# M1n_name.net
KiCad netlist of a schematic drawn in EAGLE
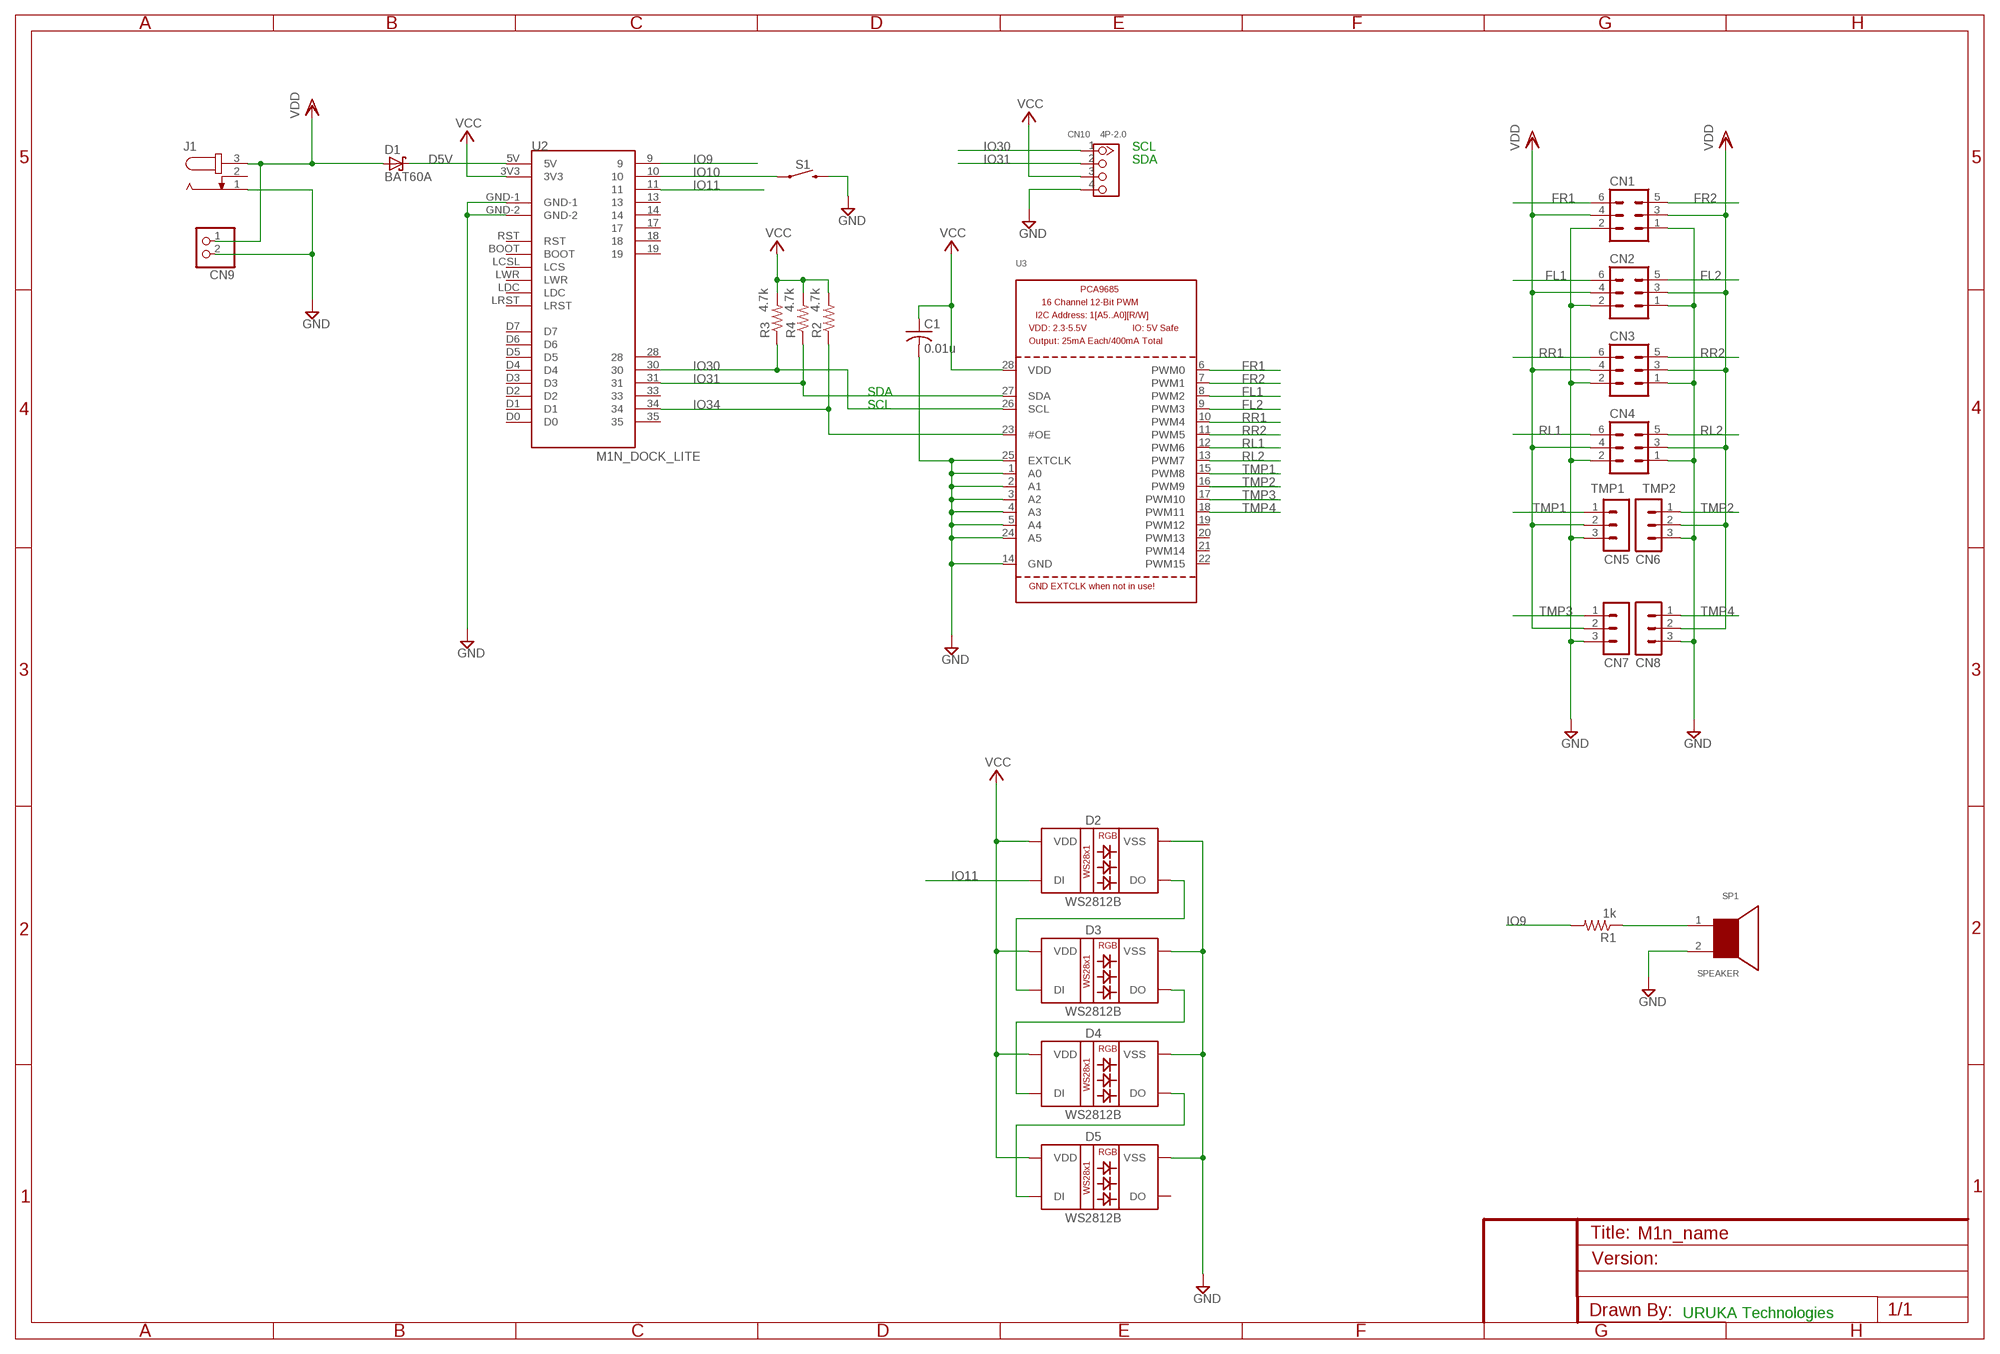
[diagram p0: schematic, sheet 1]

(export (version "E")
  (design (tool "Eeschema 10.0.6"))
  (components
    (comp (ref "C1")
      (value "0.01u")
      (footprint "eagle-import:C0603")
      (libsource (lib "eagle-import") (part "C-USC0603"))
    )
    (comp (ref "CN1")
      (value "MA03-2")
      (footprint "eagle-import:MA03-2")
      (libsource (lib "eagle-import") (part "MA03-2"))
    )
    (comp (ref "CN2")
      (value "MA03-2")
      (footprint "eagle-import:MA03-2")
      (libsource (lib "eagle-import") (part "MA03-2"))
    )
    (comp (ref "CN3")
      (value "MA03-2")
      (footprint "eagle-import:MA03-2")
      (libsource (lib "eagle-import") (part "MA03-2"))
    )
    (comp (ref "CN4")
      (value "MA03-2")
      (footprint "eagle-import:MA03-2")
      (libsource (lib "eagle-import") (part "MA03-2"))
    )
    (comp (ref "CN5")
      (value "MA03-1")
      (footprint "eagle-import:MA03-1")
      (libsource (lib "eagle-import") (part "MA03-1"))
    )
    (comp (ref "CN6")
      (value "MA03-1")
      (footprint "eagle-import:MA03-1")
      (libsource (lib "eagle-import") (part "MA03-1"))
    )
    (comp (ref "CN7")
      (value "MA03-1")
      (footprint "eagle-import:MA03-1")
      (libsource (lib "eagle-import") (part "MA03-1"))
    )
    (comp (ref "CN8")
      (value "MA03-1")
      (footprint "eagle-import:MA03-1")
      (libsource (lib "eagle-import") (part "MA03-1"))
    )
    (comp (ref "CN9")
      (value "JST_2PIN-THM")
      (footprint "eagle-import:JST-PH-2-THM")
      (libsource (lib "eagle-import") (part "JST_2PIN-THM"))
    )
    (comp (ref "CN10")
      (value "4P-2.0")
      (footprint "eagle-import:HW4-2.0")
      (libsource (lib "eagle-import") (part "GROVE-CONNECTOR-DIP(4P-2.0)"))
    )
    (comp (ref "D1")
      (value "BAT60A")
      (footprint "eagle-import:SOD323_ST")
      (libsource (lib "eagle-import") (part "BAT60A"))
    )
    (comp (ref "D2")
      (value "WS2812B")
      (footprint "eagle-import:WS2812_2020")
      (libsource (lib "eagle-import") (part "WS2812_2020"))
    )
    (comp (ref "D3")
      (value "WS2812B")
      (footprint "eagle-import:WS2812_2020")
      (libsource (lib "eagle-import") (part "WS2812_2020"))
    )
    (comp (ref "D4")
      (value "WS2812B")
      (footprint "eagle-import:WS2812_2020")
      (libsource (lib "eagle-import") (part "WS2812_2020"))
    )
    (comp (ref "D5")
      (value "WS2812B")
      (footprint "eagle-import:WS2812_2020")
      (libsource (lib "eagle-import") (part "WS2812_2020"))
    )
    (comp (ref "J1")
      (value "JACK-PLUG0")
      (footprint "eagle-import:SPC4077")
      (libsource (lib "eagle-import") (part "JACK-PLUG0"))
    )
    (comp (ref "R1")
      (value "1k")
      (footprint "eagle-import:0204_5")
      (libsource (lib "eagle-import") (part "R-US_0204/5"))
    )
    (comp (ref "R2")
      (value "4.7k")
      (footprint "eagle-import:0204_5")
      (libsource (lib "eagle-import") (part "R-US_0204/5"))
    )
    (comp (ref "R3")
      (value "4.7k")
      (footprint "eagle-import:0204_5")
      (libsource (lib "eagle-import") (part "R-US_0204/5"))
    )
    (comp (ref "R4")
      (value "4.7k")
      (footprint "eagle-import:0204_5")
      (libsource (lib "eagle-import") (part "R-US_0204/5"))
    )
    (comp (ref "S1")
      (value "MOMENTARY-SWITCH-SPST-SMD-6.0X3.5MM")
      (footprint "eagle-import:TACTILE_SWITCH_SMD_6.0X3.5MM")
      (libsource (lib "eagle-import") (part "MOMENTARY-SWITCH-SPST-SMD-6.0X3.5MM"))
    )
    (comp (ref "SP1")
      (value "SPEAKER")
      (footprint "eagle-import:SPEAKER")
      (libsource (lib "eagle-import") (part "SPEAKER"))
    )
    (comp (ref "U2")
      (value "M1N_DOCK_LITE")
      (footprint "eagle-import:M1N_DOCK_LITE")
      (libsource (lib "eagle-import") (part "M1N_DOCK_LITE"))
    )
    (comp (ref "U3")
      (value "PCA9685")
      (footprint "eagle-import:TSSOP28")
      (libsource (lib "eagle-import") (part "PCA9685"))
    )
  )
  (nets
    (net (code "1") (name "/D5V") (class "Default")
      (node (ref "D1") (pin "C") (pinfunction "C_C") (pintype "passive"))
      (node (ref "U2") (pin "5V") (pinfunction "5V_5V") (pintype "passive"))
    )
    (net (code "2") (name "/FL1") (class "Default")
      (node (ref "CN2") (pin "6") (pinfunction "6_6") (pintype "passive"))
      (node (ref "U3") (pin "8") (pinfunction "PWM2_8") (pintype "output"))
    )
    (net (code "3") (name "/FL2") (class "Default")
      (node (ref "CN2") (pin "5") (pinfunction "5_5") (pintype "passive"))
      (node (ref "U3") (pin "9") (pinfunction "PWM3_9") (pintype "output"))
    )
    (net (code "4") (name "/FR1") (class "Default")
      (node (ref "CN1") (pin "6") (pinfunction "6_6") (pintype "passive"))
      (node (ref "U3") (pin "6") (pinfunction "PWM0_6") (pintype "output"))
    )
    (net (code "5") (name "/FR2") (class "Default")
      (node (ref "CN1") (pin "5") (pinfunction "5_5") (pintype "passive"))
      (node (ref "U3") (pin "7") (pinfunction "PWM1_7") (pintype "output"))
    )
    (net (code "6") (name "/IO9") (class "Default")
      (node (ref "R1") (pin "2") (pinfunction "2_2") (pintype "passive"))
      (node (ref "U2") (pin "9") (pinfunction "9_9") (pintype "passive"))
    )
    (net (code "7") (name "/IO10") (class "Default")
      (node (ref "S1") (pin "1") (pinfunction "1_1") (pintype "passive"))
      (node (ref "U2") (pin "10") (pinfunction "10_10") (pintype "passive"))
    )
    (net (code "8") (name "/IO11") (class "Default")
      (node (ref "D2") (pin "3") (pinfunction "DI_3") (pintype "bidirectional"))
      (node (ref "U2") (pin "11") (pinfunction "11_11") (pintype "passive"))
    )
    (net (code "9") (name "/IO30") (class "Default")
      (node (ref "CN10") (pin "1") (pinfunction "1_1") (pintype "bidirectional"))
      (node (ref "R3") (pin "1") (pinfunction "1_1") (pintype "passive"))
      (node (ref "U2") (pin "30") (pinfunction "30_30") (pintype "passive"))
      (node (ref "U3") (pin "26") (pinfunction "SCL_26") (pintype "bidirectional"))
    )
    (net (code "10") (name "/IO31") (class "Default")
      (node (ref "CN10") (pin "2") (pinfunction "2_2") (pintype "bidirectional"))
      (node (ref "R4") (pin "1") (pinfunction "1_1") (pintype "passive"))
      (node (ref "U2") (pin "31") (pinfunction "31_31") (pintype "passive"))
      (node (ref "U3") (pin "27") (pinfunction "SDA_27") (pintype "bidirectional"))
    )
    (net (code "11") (name "/IO34") (class "Default")
      (node (ref "R2") (pin "1") (pinfunction "1_1") (pintype "passive"))
      (node (ref "U2") (pin "34") (pinfunction "34_34") (pintype "passive"))
      (node (ref "U3") (pin "23") (pinfunction "#OE_23") (pintype "input"))
    )
    (net (code "12") (name "/RL1") (class "Default")
      (node (ref "CN4") (pin "6") (pinfunction "6_6") (pintype "passive"))
      (node (ref "U3") (pin "12") (pinfunction "PWM6_12") (pintype "output"))
    )
    (net (code "13") (name "/RL2") (class "Default")
      (node (ref "CN4") (pin "5") (pinfunction "5_5") (pintype "passive"))
      (node (ref "U3") (pin "13") (pinfunction "PWM7_13") (pintype "output"))
    )
    (net (code "14") (name "/RR1") (class "Default")
      (node (ref "CN3") (pin "6") (pinfunction "6_6") (pintype "passive"))
      (node (ref "U3") (pin "10") (pinfunction "PWM4_10") (pintype "output"))
    )
    (net (code "15") (name "/RR2") (class "Default")
      (node (ref "CN3") (pin "5") (pinfunction "5_5") (pintype "passive"))
      (node (ref "U3") (pin "11") (pinfunction "PWM5_11") (pintype "output"))
    )
    (net (code "16") (name "/TMP1") (class "Default")
      (node (ref "CN5") (pin "1") (pinfunction "1_1") (pintype "passive"))
      (node (ref "U3") (pin "15") (pinfunction "PWM8_15") (pintype "output"))
    )
    (net (code "17") (name "/TMP2") (class "Default")
      (node (ref "CN6") (pin "1") (pinfunction "1_1") (pintype "passive"))
      (node (ref "U3") (pin "16") (pinfunction "PWM9_16") (pintype "output"))
    )
    (net (code "18") (name "/TMP3") (class "Default")
      (node (ref "CN7") (pin "1") (pinfunction "1_1") (pintype "passive"))
      (node (ref "U3") (pin "17") (pinfunction "PWM10_17") (pintype "output"))
    )
    (net (code "19") (name "/TMP4") (class "Default")
      (node (ref "CN8") (pin "1") (pinfunction "1_1") (pintype "passive"))
      (node (ref "U3") (pin "18") (pinfunction "PWM11_18") (pintype "output"))
    )
    (net (code "20") (name "GND") (class "Default")
      (node (ref "C1") (pin "2") (pinfunction "2_2") (pintype "passive"))
      (node (ref "CN1") (pin "1") (pinfunction "1_1") (pintype "passive"))
      (node (ref "CN1") (pin "2") (pinfunction "2_2") (pintype "passive"))
      (node (ref "CN10") (pin "4") (pinfunction "4_4") (pintype "bidirectional"))
      (node (ref "CN2") (pin "1") (pinfunction "1_1") (pintype "passive"))
      (node (ref "CN2") (pin "2") (pinfunction "2_2") (pintype "passive"))
      (node (ref "CN3") (pin "1") (pinfunction "1_1") (pintype "passive"))
      (node (ref "CN3") (pin "2") (pinfunction "2_2") (pintype "passive"))
      (node (ref "CN4") (pin "1") (pinfunction "1_1") (pintype "passive"))
      (node (ref "CN4") (pin "2") (pinfunction "2_2") (pintype "passive"))
      (node (ref "CN5") (pin "3") (pinfunction "3_3") (pintype "passive"))
      (node (ref "CN6") (pin "3") (pinfunction "3_3") (pintype "passive"))
      (node (ref "CN7") (pin "3") (pinfunction "3_3") (pintype "passive"))
      (node (ref "CN8") (pin "3") (pinfunction "3_3") (pintype "passive"))
      (node (ref "CN9") (pin "2") (pinfunction "1_2") (pintype "passive"))
      (node (ref "D2") (pin "2") (pinfunction "VSS_2") (pintype "bidirectional"))
      (node (ref "D3") (pin "2") (pinfunction "VSS_2") (pintype "bidirectional"))
      (node (ref "D4") (pin "2") (pinfunction "VSS_2") (pintype "bidirectional"))
      (node (ref "D5") (pin "2") (pinfunction "VSS_2") (pintype "bidirectional"))
      (node (ref "J1") (pin "1") (pinfunction "1_1") (pintype "passive"))
      (node (ref "S1") (pin "2") (pinfunction "2_2") (pintype "passive"))
      (node (ref "SP1") (pin "2") (pinfunction "2_2") (pintype "bidirectional"))
      (node (ref "U2") (pin "GND-1") (pinfunction "GND-1_GND-1") (pintype "passive"))
      (node (ref "U2") (pin "GND-2") (pinfunction "GND-2_GND-2") (pintype "passive"))
      (node (ref "U3") (pin "1") (pinfunction "A0_1") (pintype "bidirectional"))
      (node (ref "U3") (pin "14") (pinfunction "GND_14") (pintype "power_in"))
      (node (ref "U3") (pin "2") (pinfunction "A1_2") (pintype "bidirectional"))
      (node (ref "U3") (pin "24") (pinfunction "A5_24") (pintype "bidirectional"))
      (node (ref "U3") (pin "25") (pinfunction "EXTCLK_25") (pintype "input"))
      (node (ref "U3") (pin "3") (pinfunction "A2_3") (pintype "bidirectional"))
      (node (ref "U3") (pin "4") (pinfunction "A3_4") (pintype "bidirectional"))
      (node (ref "U3") (pin "5") (pinfunction "A4_5") (pintype "bidirectional"))
    )
    (net (code "21") (name "Net-(D2-DO)") (class "Default")
      (node (ref "D2") (pin "1") (pinfunction "DO_1") (pintype "bidirectional"))
      (node (ref "D3") (pin "3") (pinfunction "DI_3") (pintype "bidirectional"))
    )
    (net (code "22") (name "Net-(D3-DO)") (class "Default")
      (node (ref "D3") (pin "1") (pinfunction "DO_1") (pintype "bidirectional"))
      (node (ref "D4") (pin "3") (pinfunction "DI_3") (pintype "bidirectional"))
    )
    (net (code "23") (name "Net-(D4-DO)") (class "Default")
      (node (ref "D4") (pin "1") (pinfunction "DO_1") (pintype "bidirectional"))
      (node (ref "D5") (pin "3") (pinfunction "DI_3") (pintype "bidirectional"))
    )
    (net (code "24") (name "Net-(R1-Pad1)") (class "Default")
      (node (ref "R1") (pin "1") (pinfunction "1_1") (pintype "passive"))
      (node (ref "SP1") (pin "1") (pinfunction "1_1") (pintype "bidirectional"))
    )
    (net (code "25") (name "VCC") (class "Default")
      (node (ref "C1") (pin "1") (pinfunction "1_1") (pintype "passive"))
      (node (ref "CN10") (pin "3") (pinfunction "3_3") (pintype "bidirectional"))
      (node (ref "D2") (pin "4") (pinfunction "VDD_4") (pintype "bidirectional"))
      (node (ref "D3") (pin "4") (pinfunction "VDD_4") (pintype "bidirectional"))
      (node (ref "D4") (pin "4") (pinfunction "VDD_4") (pintype "bidirectional"))
      (node (ref "D5") (pin "4") (pinfunction "VDD_4") (pintype "bidirectional"))
      (node (ref "R2") (pin "2") (pinfunction "2_2") (pintype "passive"))
      (node (ref "R3") (pin "2") (pinfunction "2_2") (pintype "passive"))
      (node (ref "R4") (pin "2") (pinfunction "2_2") (pintype "passive"))
      (node (ref "U2") (pin "3V3") (pinfunction "3V3_3V3") (pintype "passive"))
      (node (ref "U3") (pin "28") (pinfunction "VDD_28") (pintype "power_in"))
    )
    (net (code "26") (name "VDD") (class "Default")
      (node (ref "CN1") (pin "3") (pinfunction "3_3") (pintype "passive"))
      (node (ref "CN1") (pin "4") (pinfunction "4_4") (pintype "passive"))
      (node (ref "CN2") (pin "3") (pinfunction "3_3") (pintype "passive"))
      (node (ref "CN2") (pin "4") (pinfunction "4_4") (pintype "passive"))
      (node (ref "CN3") (pin "3") (pinfunction "3_3") (pintype "passive"))
      (node (ref "CN3") (pin "4") (pinfunction "4_4") (pintype "passive"))
      (node (ref "CN4") (pin "3") (pinfunction "3_3") (pintype "passive"))
      (node (ref "CN4") (pin "4") (pinfunction "4_4") (pintype "passive"))
      (node (ref "CN5") (pin "2") (pinfunction "2_2") (pintype "passive"))
      (node (ref "CN6") (pin "2") (pinfunction "2_2") (pintype "passive"))
      (node (ref "CN7") (pin "2") (pinfunction "2_2") (pintype "passive"))
      (node (ref "CN8") (pin "2") (pinfunction "2_2") (pintype "passive"))
      (node (ref "CN9") (pin "1") (pinfunction "2_1") (pintype "passive"))
      (node (ref "D1") (pin "A") (pinfunction "A_A") (pintype "passive"))
      (node (ref "J1") (pin "3") (pinfunction "3_3") (pintype "passive"))
    )
    (net (code "27") (name "unconnected-(D5-DO-Pad1)") (class "Default")
      (node (ref "D5") (pin "1") (pinfunction "DO_1") (pintype "bidirectional"))
    )
    (net (code "28") (name "unconnected-(J1-Pad2)") (class "Default")
      (node (ref "J1") (pin "2") (pinfunction "2_2") (pintype "passive"))
    )
    (net (code "29") (name "unconnected-(U2-LCS-PadLCSL)") (class "Default")
      (node (ref "U2") (pin "LCSL") (pinfunction "LCS_LCSL") (pintype "passive"))
    )
    (net (code "30") (name "unconnected-(U2-Pad13)") (class "Default")
      (node (ref "U2") (pin "13") (pinfunction "13_13") (pintype "passive"))
    )
    (net (code "31") (name "unconnected-(U2-Pad14)") (class "Default")
      (node (ref "U2") (pin "14") (pinfunction "14_14") (pintype "passive"))
    )
    (net (code "32") (name "unconnected-(U2-Pad17)") (class "Default")
      (node (ref "U2") (pin "17") (pinfunction "17_17") (pintype "passive"))
    )
    (net (code "33") (name "unconnected-(U2-Pad18)") (class "Default")
      (node (ref "U2") (pin "18") (pinfunction "18_18") (pintype "passive"))
    )
    (net (code "34") (name "unconnected-(U2-Pad19)") (class "Default")
      (node (ref "U2") (pin "19") (pinfunction "19_19") (pintype "passive"))
    )
    (net (code "35") (name "unconnected-(U2-Pad28)") (class "Default")
      (node (ref "U2") (pin "28") (pinfunction "28_28") (pintype "passive"))
    )
    (net (code "36") (name "unconnected-(U2-Pad33)") (class "Default")
      (node (ref "U2") (pin "33") (pinfunction "33_33") (pintype "passive"))
    )
    (net (code "37") (name "unconnected-(U2-Pad35)") (class "Default")
      (node (ref "U2") (pin "35") (pinfunction "35_35") (pintype "passive"))
    )
    (net (code "38") (name "unconnected-(U2-PadBOOT)") (class "Default")
      (node (ref "U2") (pin "BOOT") (pinfunction "BOOT_BOOT") (pintype "passive"))
    )
    (net (code "39") (name "unconnected-(U2-PadD0)") (class "Default")
      (node (ref "U2") (pin "D0") (pinfunction "D0_D0") (pintype "passive"))
    )
    (net (code "40") (name "unconnected-(U2-PadD1)") (class "Default")
      (node (ref "U2") (pin "D1") (pinfunction "D1_D1") (pintype "passive"))
    )
    (net (code "41") (name "unconnected-(U2-PadD2)") (class "Default")
      (node (ref "U2") (pin "D2") (pinfunction "D2_D2") (pintype "passive"))
    )
    (net (code "42") (name "unconnected-(U2-PadD3)") (class "Default")
      (node (ref "U2") (pin "D3") (pinfunction "D3_D3") (pintype "passive"))
    )
    (net (code "43") (name "unconnected-(U2-PadD4)") (class "Default")
      (node (ref "U2") (pin "D4") (pinfunction "D4_D4") (pintype "passive"))
    )
    (net (code "44") (name "unconnected-(U2-PadD5)") (class "Default")
      (node (ref "U2") (pin "D5") (pinfunction "D5_D5") (pintype "passive"))
    )
    (net (code "45") (name "unconnected-(U2-PadD6)") (class "Default")
      (node (ref "U2") (pin "D6") (pinfunction "D6_D6") (pintype "passive"))
    )
    (net (code "46") (name "unconnected-(U2-PadD7)") (class "Default")
      (node (ref "U2") (pin "D7") (pinfunction "D7_D7") (pintype "passive"))
    )
    (net (code "47") (name "unconnected-(U2-PadLDC)") (class "Default")
      (node (ref "U2") (pin "LDC") (pinfunction "LDC_LDC") (pintype "passive"))
    )
    (net (code "48") (name "unconnected-(U2-PadLRST)") (class "Default")
      (node (ref "U2") (pin "LRST") (pinfunction "LRST_LRST") (pintype "passive"))
    )
    (net (code "49") (name "unconnected-(U2-PadLWR)") (class "Default")
      (node (ref "U2") (pin "LWR") (pinfunction "LWR_LWR") (pintype "passive"))
    )
    (net (code "50") (name "unconnected-(U2-PadRST)") (class "Default")
      (node (ref "U2") (pin "RST") (pinfunction "RST_RST") (pintype "passive"))
    )
    (net (code "51") (name "unconnected-(U3-PWM12-Pad19)") (class "Default")
      (node (ref "U3") (pin "19") (pinfunction "PWM12_19") (pintype "output"))
    )
    (net (code "52") (name "unconnected-(U3-PWM13-Pad20)") (class "Default")
      (node (ref "U3") (pin "20") (pinfunction "PWM13_20") (pintype "output"))
    )
    (net (code "53") (name "unconnected-(U3-PWM14-Pad21)") (class "Default")
      (node (ref "U3") (pin "21") (pinfunction "PWM14_21") (pintype "output"))
    )
    (net (code "54") (name "unconnected-(U3-PWM15-Pad22)") (class "Default")
      (node (ref "U3") (pin "22") (pinfunction "PWM15_22") (pintype "output"))
    )
  )
)
